# TinLi.net
KiCad netlist of a schematic drawn in EAGLE
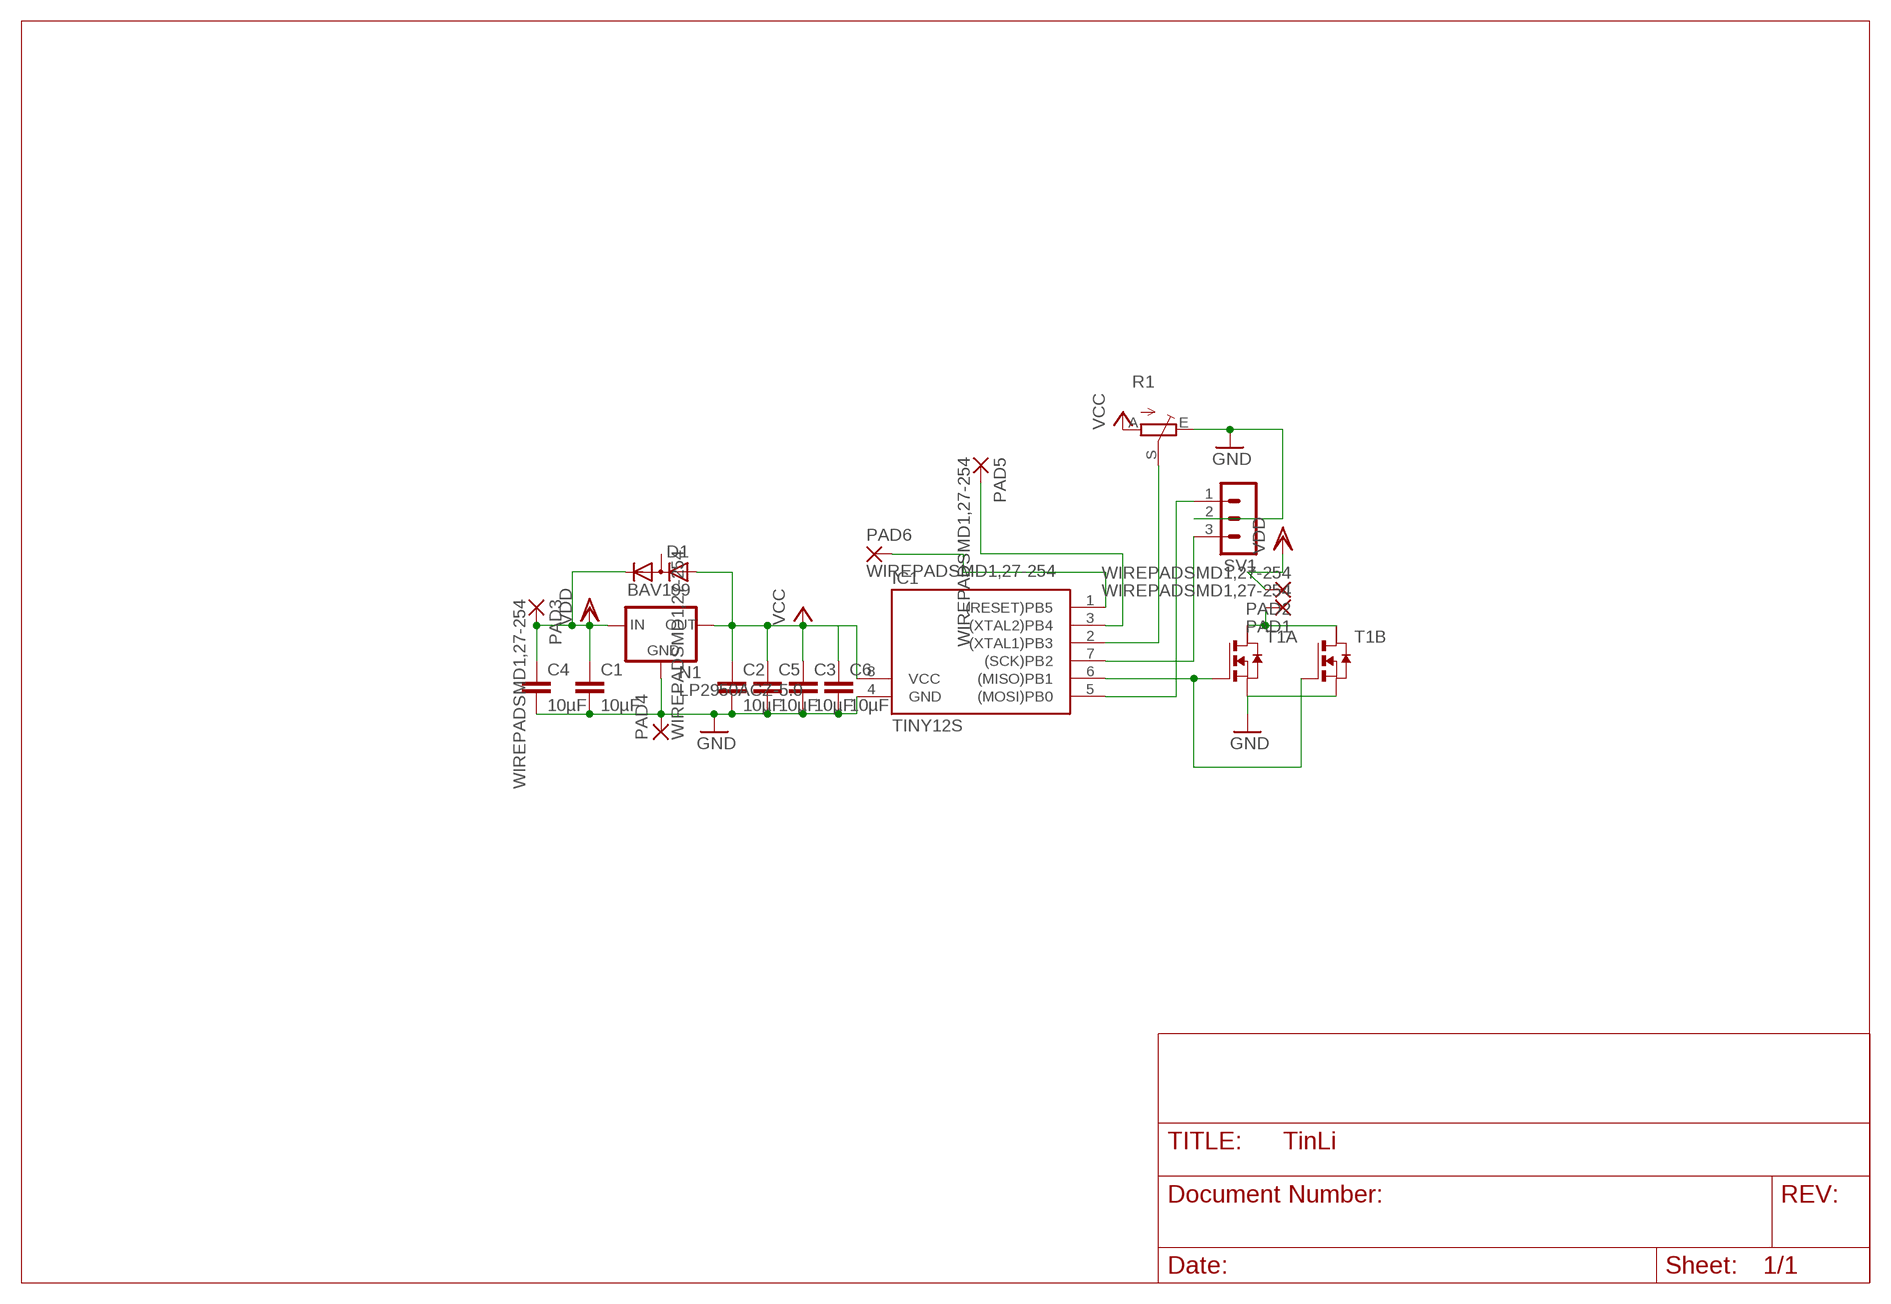
[diagram p0: schematic, sheet 1]

(export (version "E")
  (design (tool "Eeschema 10.0.6"))
  (components
    (comp (ref "C1")
      (value "10µF")
      (footprint "eagle-import:C1206")
      (libsource (lib "eagle-import") (part "C-EUC1206"))
    )
    (comp (ref "C2")
      (value "10µF")
      (footprint "eagle-import:C1206")
      (libsource (lib "eagle-import") (part "C-EUC1206"))
    )
    (comp (ref "C3")
      (value "10µF")
      (footprint "eagle-import:C1206")
      (libsource (lib "eagle-import") (part "C-EUC1206"))
    )
    (comp (ref "C4")
      (value "10µF")
      (footprint "eagle-import:C1206")
      (libsource (lib "eagle-import") (part "C-EUC1206"))
    )
    (comp (ref "C5")
      (value "10µF")
      (footprint "eagle-import:C1206")
      (libsource (lib "eagle-import") (part "C-EUC1206"))
    )
    (comp (ref "C6")
      (value "10µF")
      (footprint "eagle-import:C1206")
      (libsource (lib "eagle-import") (part "C-EUC1206"))
    )
    (comp (ref "D1")
      (value "BAV199")
      (footprint "eagle-import:SOT23")
      (libsource (lib "eagle-import") (part "BAV199"))
    )
    (comp (ref "IC1")
      (value "TINY12S")
      (footprint "eagle-import:SOIC8")
      (libsource (lib "eagle-import") (part "TINY12S"))
    )
    (comp (ref "N1")
      (value "LP2950ACZ-5.0")
      (footprint "eagle-import:TO92")
      (libsource (lib "eagle-import") (part "LP2950?ACZ-5.0"))
    )
    (comp (ref "PAD1")
      (value "WIREPADSMD1,27-254")
      (footprint "eagle-import:SMD1,27-2,54")
      (libsource (lib "eagle-import") (part "WIREPADSMD1,27-254"))
    )
    (comp (ref "PAD2")
      (value "WIREPADSMD1,27-254")
      (footprint "eagle-import:SMD1,27-2,54")
      (libsource (lib "eagle-import") (part "WIREPADSMD1,27-254"))
    )
    (comp (ref "PAD3")
      (value "WIREPADSMD1,27-254")
      (footprint "eagle-import:SMD1,27-2,54")
      (libsource (lib "eagle-import") (part "WIREPADSMD1,27-254"))
    )
    (comp (ref "PAD4")
      (value "WIREPADSMD1,27-254")
      (footprint "eagle-import:SMD1,27-2,54")
      (libsource (lib "eagle-import") (part "WIREPADSMD1,27-254"))
    )
    (comp (ref "PAD5")
      (value "WIREPADSMD1,27-254")
      (footprint "eagle-import:SMD1,27-2,54")
      (libsource (lib "eagle-import") (part "WIREPADSMD1,27-254"))
    )
    (comp (ref "PAD6")
      (value "WIREPADSMD1,27-254")
      (footprint "eagle-import:SMD1,27-2,54")
      (libsource (lib "eagle-import") (part "WIREPADSMD1,27-254"))
    )
    (comp (ref "R1")
      (value "TRIM_EU-CA6V")
      (footprint "eagle-import:CA6V")
      (libsource (lib "eagle-import") (part "TRIM_EU-CA6V"))
    )
    (comp (ref "SV1")
      (value "MA03-1")
      (footprint "eagle-import:MA03-1")
      (libsource (lib "eagle-import") (part "MA03-1"))
    )
    (comp (ref "T1")
      (value "NMOS2SO8")
      (footprint "eagle-import:SO8")
      (libsource (lib "eagle-import") (part "NMOS2SO8"))
    )
  )
  (nets
    (net (code "1") (name "GND") (class "Default")
      (node (ref "C1") (pin "2") (pinfunction "2_2") (pintype "passive"))
      (node (ref "C2") (pin "2") (pinfunction "2_2") (pintype "passive"))
      (node (ref "C3") (pin "2") (pinfunction "2_2") (pintype "passive"))
      (node (ref "C4") (pin "2") (pinfunction "2_2") (pintype "passive"))
      (node (ref "C5") (pin "2") (pinfunction "2_2") (pintype "passive"))
      (node (ref "C6") (pin "2") (pinfunction "2_2") (pintype "passive"))
      (node (ref "IC1") (pin "4") (pinfunction "GND_4") (pintype "power_in"))
      (node (ref "N1") (pin "2") (pinfunction "GND_2") (pintype "input"))
      (node (ref "PAD4") (pin "1") (pinfunction "P_1") (pintype "passive"))
      (node (ref "R1") (pin "E") (pinfunction "E_E") (pintype "passive"))
      (node (ref "SV1") (pin "2") (pinfunction "2_2") (pintype "passive"))
      (node (ref "T1") (pin "1") (pinfunction "S_1") (pintype "passive"))
      (node (ref "T1") (pin "3") (pinfunction "S_3") (pintype "passive"))
    )
    (net (code "2") (name "Net-(IC1-(MISO)PB1)") (class "Default")
      (node (ref "IC1") (pin "6") (pinfunction "(MISO)PB1_6") (pintype "bidirectional"))
      (node (ref "T1") (pin "2") (pinfunction "G_2") (pintype "passive"))
      (node (ref "T1") (pin "4") (pinfunction "G_4") (pintype "passive"))
    )
    (net (code "3") (name "Net-(IC1-(MOSI)PB0)") (class "Default")
      (node (ref "IC1") (pin "5") (pinfunction "(MOSI)PB0_5") (pintype "bidirectional"))
      (node (ref "SV1") (pin "1") (pinfunction "1_1") (pintype "passive"))
    )
    (net (code "4") (name "Net-(IC1-(RESET)PB5)") (class "Default")
      (node (ref "IC1") (pin "1") (pinfunction "(RESET)PB5_1") (pintype "bidirectional"))
      (node (ref "PAD6") (pin "1") (pinfunction "P_1") (pintype "passive"))
    )
    (net (code "5") (name "Net-(IC1-(SCK)PB2)") (class "Default")
      (node (ref "IC1") (pin "7") (pinfunction "(SCK)PB2_7") (pintype "bidirectional"))
      (node (ref "SV1") (pin "3") (pinfunction "3_3") (pintype "passive"))
    )
    (net (code "6") (name "Net-(IC1-(XTAL1)PB3)") (class "Default")
      (node (ref "IC1") (pin "2") (pinfunction "(XTAL1)PB3_2") (pintype "bidirectional"))
      (node (ref "R1") (pin "S") (pinfunction "S_S") (pintype "passive"))
    )
    (net (code "7") (name "Net-(IC1-(XTAL2)PB4)") (class "Default")
      (node (ref "IC1") (pin "3") (pinfunction "(XTAL2)PB4_3") (pintype "bidirectional"))
      (node (ref "PAD5") (pin "1") (pinfunction "P_1") (pintype "passive"))
    )
    (net (code "8") (name "Net-(PAD1-P)") (class "Default")
      (node (ref "PAD1") (pin "1") (pinfunction "P_1") (pintype "passive"))
      (node (ref "T1") (pin "6") (pinfunction "D_6") (pintype "passive"))
      (node (ref "T1") (pin "8") (pinfunction "D_8") (pintype "passive"))
    )
    (net (code "9") (name "VCC") (class "Default")
      (node (ref "C2") (pin "1") (pinfunction "1_1") (pintype "passive"))
      (node (ref "C3") (pin "1") (pinfunction "1_1") (pintype "passive"))
      (node (ref "C5") (pin "1") (pinfunction "1_1") (pintype "passive"))
      (node (ref "C6") (pin "1") (pinfunction "1_1") (pintype "passive"))
      (node (ref "D1") (pin "1") (pinfunction "A_1") (pintype "passive"))
      (node (ref "IC1") (pin "8") (pinfunction "VCC_8") (pintype "power_in"))
      (node (ref "N1") (pin "1") (pinfunction "OUT_1") (pintype "passive"))
      (node (ref "R1") (pin "A") (pinfunction "A_A") (pintype "passive"))
    )
    (net (code "10") (name "VDD") (class "Default")
      (node (ref "C1") (pin "1") (pinfunction "1_1") (pintype "passive"))
      (node (ref "C4") (pin "1") (pinfunction "1_1") (pintype "passive"))
      (node (ref "D1") (pin "2") (pinfunction "C_2") (pintype "passive"))
      (node (ref "N1") (pin "3") (pinfunction "IN_3") (pintype "input"))
      (node (ref "PAD2") (pin "1") (pinfunction "P_1") (pintype "passive"))
      (node (ref "PAD3") (pin "1") (pinfunction "P_1") (pintype "passive"))
    )
    (net (code "11") (name "unconnected-(D1-AC-Pad3)") (class "Default")
      (node (ref "D1") (pin "3") (pinfunction "AC_3") (pintype "passive"))
    )
    (net (code "12") (name "unconnected-(T1A-D2-Pad7)") (class "Default")
      (node (ref "T1") (pin "7") (pinfunction "D2_7") (pintype "passive"))
    )
    (net (code "13") (name "unconnected-(T1B-D2-Pad5)") (class "Default")
      (node (ref "T1") (pin "5") (pinfunction "D2_5") (pintype "passive"))
    )
  )
)
